# design.net
KiCad netlist of a schematic drawn in EasyEDA Pro
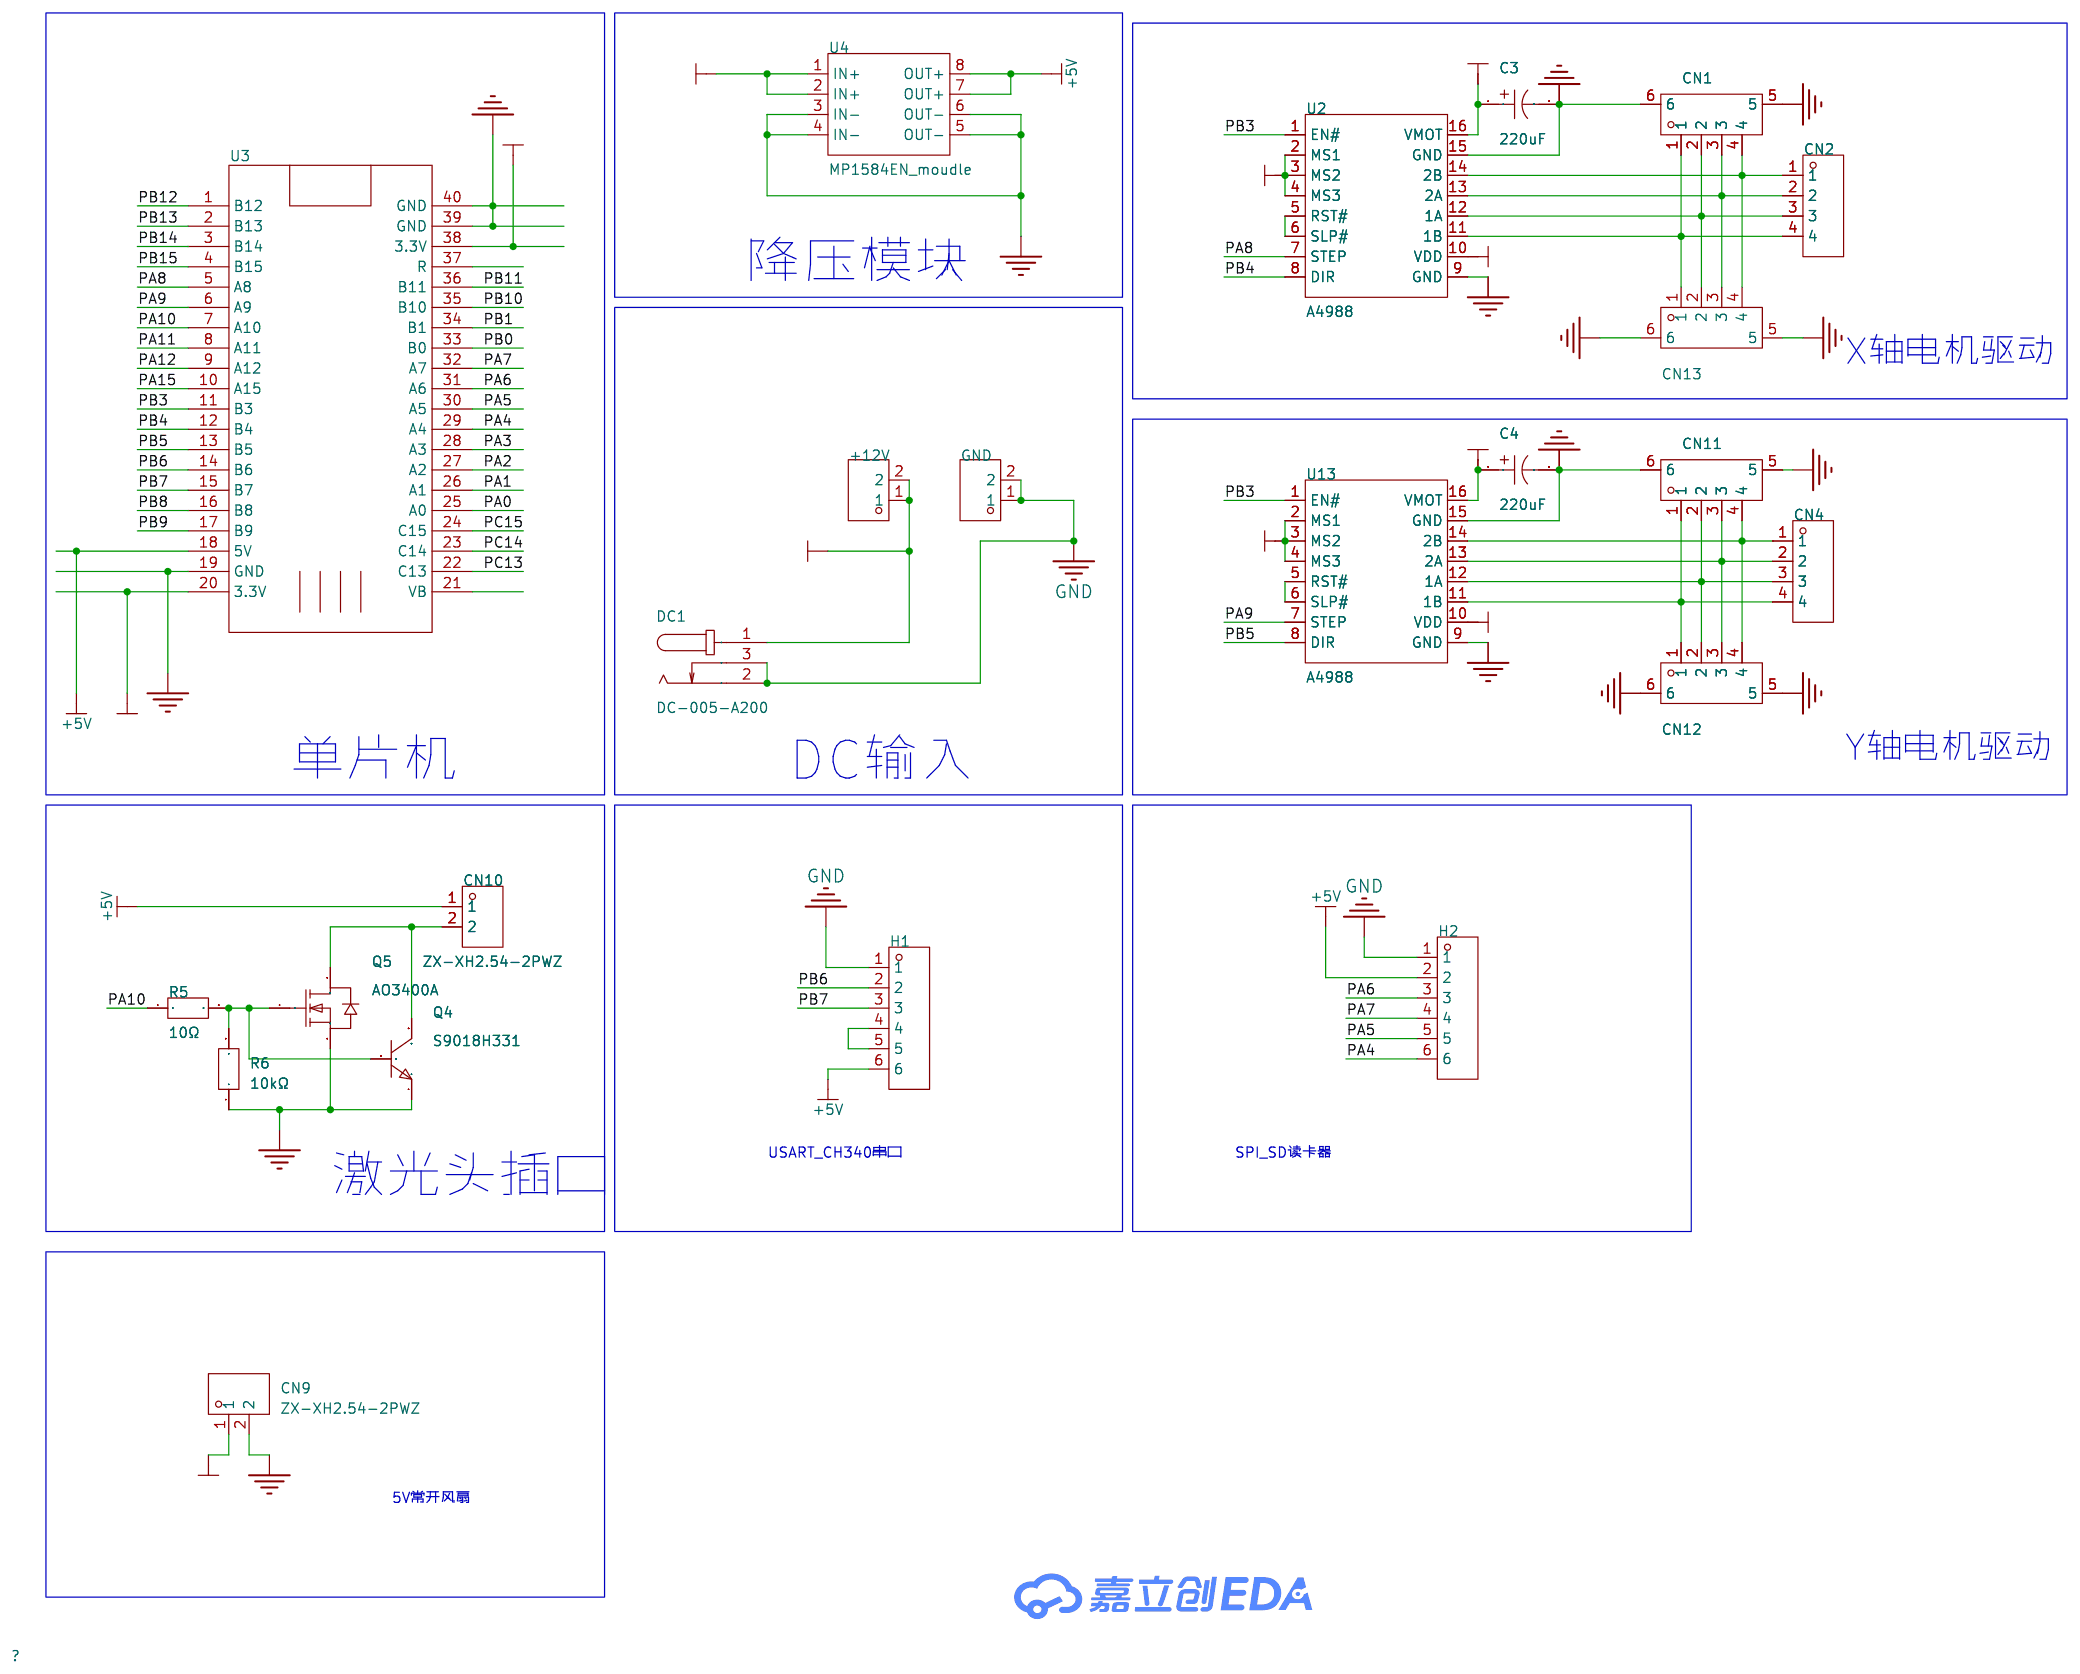
[diagram p0: schematic sheet]

(export (version "E")
  (design (tool "Eeschema 10.0.6"))
  (components
    (comp (ref "+12V")
      (value "~")
      (description "2.54 1*2P 直排针 0.8u镀金 PBT RoHS,针长3*6mm")
      (fields
        (field (name "Manufacturer Part") "Z-211-0211-0021-001")
        (field (name "Manufacturer") "Nextron(台湾正凌)")
      )
      (libsource (lib "easyedapro") (part "Z-211-0211-0021-001"))
    )
    (comp (ref "C3")
      (value "220uF")
      (footprint "easyedapro:CAP-TH_BD8.0-P3.50-D0.6-FD")
      (description "容值:220uF;精度:±20%;额定电压:25V;纹波电流:-;等效串联电阻(ESR):-;")
      (fields
        (field (name "Manufacturer Part") "RA3-25V221MG3#-F1")
        (field (name "Manufacturer") "TAIYO YUDEN(太诱)")
      )
      (libsource (lib "easyedapro") (part "RA3-25V221MG3#-F1"))
    )
    (comp (ref "C4")
      (value "220uF")
      (footprint "easyedapro:CAP-TH_BD8.0-P3.50-D0.6-FD")
      (description "容值:220uF;精度:±20%;额定电压:25V;纹波电流:-;等效串联电阻(ESR):-;")
      (fields
        (field (name "Manufacturer Part") "RA3-25V221MG3#-F1")
        (field (name "Manufacturer") "TAIYO YUDEN(太诱)")
      )
      (libsource (lib "easyedapro") (part "RA3-25V221MG3#-F1"))
    )
    (comp (ref "CN1")
      (value "AFA07-S04ECC-00")
      (footprint "easyedapro:FPC-SMD_4P-P1.00_AFA07-S04ECC-00")
      (description "锁定特性:抽屉式;触点类型:上接;触点数量:4P;间距:1mm;安装类型:卧贴;")
      (fields (field (name "Manufacturer") "JS(钜硕电子)"))
      (libsource (lib "easyedapro") (part "FPCPull type Pick up H3.0mm"))
    )
    (comp (ref "CN2")
      (value "2.54-1*4P母")
      (footprint "easyedapro:HDR-TH_4P-P2.54-V-F")
      (fields (field (name "Manufacturer") "BOOMELE(博穆精密)"))
      (libsource (lib "easyedapro") (part "2.54-1*4P母"))
    )
    (comp (ref "CN4")
      (value "2.54-1*4P母")
      (footprint "easyedapro:HDR-TH_4P-P2.54-V-F")
      (fields (field (name "Manufacturer") "BOOMELE(博穆精密)"))
      (libsource (lib "easyedapro") (part "2.54-1*4P母"))
    )
    (comp (ref "CN9")
      (value "ZX-XH2.54-2PWZ")
      (footprint "easyedapro:CONN-TH_2P-P2.50_ZX-XH2.54-2PWZ")
      (fields (field (name "Manufacturer") "Megastar(兆星)"))
      (libsource (lib "easyedapro") (part "ZX-XH2.54-2PWZ"))
    )
    (comp (ref "CN10")
      (value "ZX-XH2.54-2PWZ")
      (footprint "easyedapro:CONN-TH_2P-P2.50_ZX-XH2.54-2PWZ")
      (fields (field (name "Manufacturer") "Megastar(兆星)"))
      (libsource (lib "easyedapro") (part "ZX-XH2.54-2PWZ"))
    )
    (comp (ref "CN11")
      (value "AFA07-S04ECC-00")
      (footprint "easyedapro:FPC-SMD_4P-P1.00_AFA07-S04ECC-00")
      (description "锁定特性:抽屉式;触点类型:上接;触点数量:4P;间距:1mm;安装类型:卧贴;")
      (fields (field (name "Manufacturer") "JS(钜硕电子)"))
      (libsource (lib "easyedapro") (part "FPCPull type Pick up H3.0mm"))
    )
    (comp (ref "CN12")
      (value "AFA07-S04ECC-00")
      (footprint "easyedapro:FPC-SMD_4P-P1.00_AFA07-S04ECC-00")
      (description "锁定特性:抽屉式;触点类型:上接;触点数量:4P;间距:1mm;安装类型:卧贴;")
      (fields (field (name "Manufacturer") "JS(钜硕电子)"))
      (libsource (lib "easyedapro") (part "FPCPull type Pick up H3.0mm"))
    )
    (comp (ref "CN13")
      (value "AFA07-S04ECC-00")
      (footprint "easyedapro:FPC-SMD_4P-P1.00_AFA07-S04ECC-00")
      (description "锁定特性:抽屉式;触点类型:上接;触点数量:4P;间距:1mm;安装类型:卧贴;")
      (fields (field (name "Manufacturer") "JS(钜硕电子)"))
      (libsource (lib "easyedapro") (part "FPCPull type Pick up H3.0mm"))
    )
    (comp (ref "DC1")
      (value "DC-005-A200")
      (footprint "easyedapro:DC-IN-TH_DC-005-A200")
      (description "连接器类型:DC电源插座;安装方式:弯插;触点内径:2mm;触点外径:6.4mm;额定电流:3A;额定电压:30V;工作温度:-20°C~+70°C;")
      (fields (field (name "Manufacturer") "XUNPU(讯普)"))
      (libsource (lib "easyedapro") (part "DC-005-A200"))
    )
    (comp (ref "GND")
      (value "~")
      (description "2.54 1*2P 直排针 0.8u镀金 PBT RoHS,针长3*6mm")
      (fields
        (field (name "Manufacturer Part") "Z-211-0211-0021-001")
        (field (name "Manufacturer") "Nextron(台湾正凌)")
      )
      (libsource (lib "easyedapro") (part "Z-211-0211-0021-001"))
    )
    (comp (ref "H1")
      (value "~")
      (footprint "easyedapro:HDR-TH_6P-P2.54-V-F")
      (libsource (lib "easyedapro") (part "Header-Female-2.54_1x6"))
    )
    (comp (ref "H2")
      (value "~")
      (footprint "easyedapro:HDR-TH_6P-P2.54-V-F")
      (libsource (lib "easyedapro") (part "Header-Female-2.54_1x6"))
    )
    (comp (ref "Q4")
      (value "S9018H331")
      (footprint "easyedapro:TO-92-3_L4.8-W3.7-P1.27-L-1")
      (fields (field (name "Manufacturer") "ALJ(龙晶微)"))
      (libsource (lib "easyedapro") (part "S9018H331"))
    )
    (comp (ref "Q5")
      (value "AO3400A")
      (footprint "easyedapro:SOT-23-3_L2.9-W1.3-P1.90-LS2.4-BR")
      (description "数量:-;漏源电压(Vdss):30V;连续漏极电流(Id):-;导通电阻(RDS(on)):48mΩ@2.5V;耗散功率(Pd):-;阈值电压(Vgs(th)):1.45V@250uA;")
      (fields (field (name "Manufacturer") "AOS"))
      (libsource (lib "easyedapro") (part "AO3400A"))
    )
    (comp (ref "R5")
      (value "10Ω")
      (footprint "easyedapro:R0603")
      (description "电阻类型:薄膜电阻;阻值:10Ω;精度:±0.1%;功率:100mW;工作电压:75V;温度系数:±25ppm/°C;")
      (fields (field (name "Manufacturer Part") "AT0603BRD0710RL") (field (name "Manufacturer") "YAGEO(国巨)"))
      (libsource (lib "easyedapro") (part "AT0603BRD0710RL"))
    )
    (comp (ref "R6")
      (value "10kΩ")
      (footprint "easyedapro:R0805")
      (description "电阻类型:厚膜电阻;阻值:10kΩ;精度:±1%;功率:500mW;温度系数:±100ppm/°C;")
      (fields (field (name "Manufacturer Part") "SDR10EZPF1002") (field (name "Manufacturer") "ROHM(罗姆)"))
      (libsource (lib "easyedapro") (part "SDR10EZPF1002"))
    )
    (comp (ref "U2")
      (value "A4988")
      (footprint "easyedapro:DIP-16_L20.3-W15.2-P2.54_LS12.7_A4988")
      (libsource (lib "easyedapro") (part "A4988"))
    )
    (comp (ref "U3") (value "~") (libsource (lib "easyedapro") (part "STM32F103C8T6核心板")))
    (comp (ref "U4")
      (value "MP1584EN_moudle")
      (footprint "easyedapro:PWRM-TH_MP1584EN_MOUDLE")
      (libsource (lib "easyedapro") (part "MP1584EN_MOUDLE"))
    )
    (comp (ref "U13")
      (value "A4988")
      (footprint "easyedapro:DIP-16_L20.3-W15.2-P2.54_LS12.7_A4988")
      (libsource (lib "easyedapro") (part "A4988"))
    )
  )
  (nets
    (net (code "1") (name "+3.3V") (class "Default")
      (node (ref "U3") (pin "20") (pinfunction "3.3V_20") (pintype "unspecified"))
      (node (ref "U3") (pin "38") (pinfunction "3.3V_38") (pintype "unspecified"))
    )
    (net (code "2") (name "+5V") (class "Default")
      (node (ref "CN10") (pin "1") (pinfunction "1_1") (pintype "unspecified"))
      (node (ref "CN9") (pin "1") (pinfunction "1_1") (pintype "unspecified"))
      (node (ref "H1") (pin "6") (pinfunction "6_6") (pintype "unspecified"))
      (node (ref "H2") (pin "2") (pinfunction "2_2") (pintype "unspecified"))
      (node (ref "U13") (pin "10") (pinfunction "VDD_10") (pintype "unspecified"))
      (node (ref "U13") (pin "2") (pinfunction "MS1_2") (pintype "unspecified"))
      (node (ref "U13") (pin "3") (pinfunction "MS2_3") (pintype "unspecified"))
      (node (ref "U13") (pin "4") (pinfunction "MS3_4") (pintype "unspecified"))
      (node (ref "U2") (pin "10") (pinfunction "VDD_10") (pintype "unspecified"))
      (node (ref "U2") (pin "2") (pinfunction "MS1_2") (pintype "unspecified"))
      (node (ref "U2") (pin "3") (pinfunction "MS2_3") (pintype "unspecified"))
      (node (ref "U2") (pin "4") (pinfunction "MS3_4") (pintype "unspecified"))
      (node (ref "U3") (pin "18") (pinfunction "5V_18") (pintype "unspecified"))
      (node (ref "U4") (pin "7") (pinfunction "OUT+_7") (pintype "unspecified"))
      (node (ref "U4") (pin "8") (pinfunction "OUT+_8") (pintype "unspecified"))
    )
    (net (code "3") (name "+12V") (class "Default")
      (node (ref "+12V") (pin "1") (pinfunction "1_1") (pintype "input"))
      (node (ref "+12V") (pin "2") (pinfunction "2_2") (pintype "input"))
      (node (ref "C3") (pin "1") (pinfunction "1_1") (pintype "input"))
      (node (ref "C4") (pin "1") (pinfunction "1_1") (pintype "input"))
      (node (ref "DC1") (pin "1") (pinfunction "1_1") (pintype "unspecified"))
      (node (ref "U13") (pin "16") (pinfunction "VMOT_16") (pintype "unspecified"))
      (node (ref "U2") (pin "16") (pinfunction "VMOT_16") (pintype "unspecified"))
      (node (ref "U4") (pin "1") (pinfunction "IN+_1") (pintype "unspecified"))
      (node (ref "U4") (pin "2") (pinfunction "IN+_2") (pintype "unspecified"))
    )
    (net (code "4") (name "/PA0") (class "Default")
      (node (ref "U3") (pin "25") (pinfunction "A0_25") (pintype "unspecified"))
    )
    (net (code "5") (name "/PA1") (class "Default")
      (node (ref "U3") (pin "26") (pinfunction "A1_26") (pintype "unspecified"))
    )
    (net (code "6") (name "/PA2") (class "Default")
      (node (ref "U3") (pin "27") (pinfunction "A2_27") (pintype "unspecified"))
    )
    (net (code "7") (name "/PA3") (class "Default")
      (node (ref "U3") (pin "28") (pinfunction "A3_28") (pintype "unspecified"))
    )
    (net (code "8") (name "/PA4") (class "Default")
      (node (ref "H2") (pin "6") (pinfunction "6_6") (pintype "unspecified"))
      (node (ref "U3") (pin "29") (pinfunction "A4_29") (pintype "unspecified"))
    )
    (net (code "9") (name "/PA5") (class "Default")
      (node (ref "H2") (pin "5") (pinfunction "5_5") (pintype "unspecified"))
      (node (ref "U3") (pin "30") (pinfunction "A5_30") (pintype "unspecified"))
    )
    (net (code "10") (name "/PA6") (class "Default")
      (node (ref "H2") (pin "3") (pinfunction "3_3") (pintype "unspecified"))
      (node (ref "U3") (pin "31") (pinfunction "A6_31") (pintype "unspecified"))
    )
    (net (code "11") (name "/PA7") (class "Default")
      (node (ref "H2") (pin "4") (pinfunction "4_4") (pintype "unspecified"))
      (node (ref "U3") (pin "32") (pinfunction "A7_32") (pintype "unspecified"))
    )
    (net (code "12") (name "/PA8") (class "Default")
      (node (ref "U2") (pin "7") (pinfunction "STEP_7") (pintype "unspecified"))
      (node (ref "U3") (pin "5") (pinfunction "A8_5") (pintype "unspecified"))
    )
    (net (code "13") (name "/PA9") (class "Default")
      (node (ref "U13") (pin "7") (pinfunction "STEP_7") (pintype "unspecified"))
      (node (ref "U3") (pin "6") (pinfunction "A9_6") (pintype "unspecified"))
    )
    (net (code "14") (name "/PA10") (class "Default")
      (node (ref "R5") (pin "1") (pinfunction "1_1") (pintype "unspecified"))
      (node (ref "U3") (pin "7") (pinfunction "A10_7") (pintype "unspecified"))
    )
    (net (code "15") (name "/PA11") (class "Default")
      (node (ref "U3") (pin "8") (pinfunction "A11_8") (pintype "unspecified"))
    )
    (net (code "16") (name "/PA12") (class "Default")
      (node (ref "U3") (pin "9") (pinfunction "A12_9") (pintype "unspecified"))
    )
    (net (code "17") (name "/PA15") (class "Default")
      (node (ref "U3") (pin "10") (pinfunction "A15_10") (pintype "unspecified"))
    )
    (net (code "18") (name "/PB0") (class "Default")
      (node (ref "U3") (pin "33") (pinfunction "B0_33") (pintype "unspecified"))
    )
    (net (code "19") (name "/PB1") (class "Default")
      (node (ref "U3") (pin "34") (pinfunction "B1_34") (pintype "unspecified"))
    )
    (net (code "20") (name "/PB3") (class "Default")
      (node (ref "U13") (pin "1") (pinfunction "EN#_1") (pintype "unspecified"))
      (node (ref "U2") (pin "1") (pinfunction "EN#_1") (pintype "unspecified"))
      (node (ref "U3") (pin "11") (pinfunction "B3_11") (pintype "unspecified"))
    )
    (net (code "21") (name "/PB4") (class "Default")
      (node (ref "U2") (pin "8") (pinfunction "DIR_8") (pintype "unspecified"))
      (node (ref "U3") (pin "12") (pinfunction "B4_12") (pintype "unspecified"))
    )
    (net (code "22") (name "/PB5") (class "Default")
      (node (ref "U13") (pin "8") (pinfunction "DIR_8") (pintype "unspecified"))
      (node (ref "U3") (pin "13") (pinfunction "B5_13") (pintype "unspecified"))
    )
    (net (code "23") (name "/PB6") (class "Default")
      (node (ref "H1") (pin "2") (pinfunction "2_2") (pintype "unspecified"))
      (node (ref "U3") (pin "14") (pinfunction "B6_14") (pintype "unspecified"))
    )
    (net (code "24") (name "/PB7") (class "Default")
      (node (ref "H1") (pin "3") (pinfunction "3_3") (pintype "unspecified"))
      (node (ref "U3") (pin "15") (pinfunction "B7_15") (pintype "unspecified"))
    )
    (net (code "25") (name "/PB8") (class "Default")
      (node (ref "U3") (pin "16") (pinfunction "B8_16") (pintype "unspecified"))
    )
    (net (code "26") (name "/PB9") (class "Default")
      (node (ref "U3") (pin "17") (pinfunction "B9_17") (pintype "unspecified"))
    )
    (net (code "27") (name "/PB10") (class "Default")
      (node (ref "U3") (pin "35") (pinfunction "B10_35") (pintype "unspecified"))
    )
    (net (code "28") (name "/PB11") (class "Default")
      (node (ref "U3") (pin "36") (pinfunction "B11_36") (pintype "unspecified"))
    )
    (net (code "29") (name "/PB12") (class "Default")
      (node (ref "U3") (pin "1") (pinfunction "B12_1") (pintype "unspecified"))
    )
    (net (code "30") (name "/PB13") (class "Default")
      (node (ref "U3") (pin "2") (pinfunction "B13_2") (pintype "unspecified"))
    )
    (net (code "31") (name "/PB14") (class "Default")
      (node (ref "U3") (pin "3") (pinfunction "B14_3") (pintype "unspecified"))
    )
    (net (code "32") (name "/PB15") (class "Default")
      (node (ref "U3") (pin "4") (pinfunction "B15_4") (pintype "unspecified"))
    )
    (net (code "33") (name "/PC13") (class "Default")
      (node (ref "U3") (pin "22") (pinfunction "C13_22") (pintype "unspecified"))
    )
    (net (code "34") (name "/PC14") (class "Default")
      (node (ref "U3") (pin "23") (pinfunction "C14_23") (pintype "unspecified"))
    )
    (net (code "35") (name "/PC15") (class "Default")
      (node (ref "U3") (pin "24") (pinfunction "C15_24") (pintype "unspecified"))
    )
    (net (code "36") (name "GND") (class "Default")
      (node (ref "C3") (pin "2") (pinfunction "2_2") (pintype "input"))
      (node (ref "C4") (pin "2") (pinfunction "2_2") (pintype "input"))
      (node (ref "CN1") (pin "5") (pinfunction "5_5") (pintype "unspecified"))
      (node (ref "CN1") (pin "6") (pinfunction "6_6") (pintype "unspecified"))
      (node (ref "CN11") (pin "5") (pinfunction "5_5") (pintype "unspecified"))
      (node (ref "CN11") (pin "6") (pinfunction "6_6") (pintype "unspecified"))
      (node (ref "CN12") (pin "5") (pinfunction "5_5") (pintype "unspecified"))
      (node (ref "CN12") (pin "6") (pinfunction "6_6") (pintype "unspecified"))
      (node (ref "CN13") (pin "5") (pinfunction "5_5") (pintype "unspecified"))
      (node (ref "CN13") (pin "6") (pinfunction "6_6") (pintype "unspecified"))
      (node (ref "CN9") (pin "2") (pinfunction "2_2") (pintype "unspecified"))
      (node (ref "DC1") (pin "2") (pinfunction "2_2") (pintype "unspecified"))
      (node (ref "DC1") (pin "3") (pinfunction "3_3") (pintype "unspecified"))
      (node (ref "GND") (pin "1") (pinfunction "1_1") (pintype "input"))
      (node (ref "GND") (pin "2") (pinfunction "2_2") (pintype "input"))
      (node (ref "H1") (pin "1") (pinfunction "1_1") (pintype "unspecified"))
      (node (ref "H2") (pin "1") (pinfunction "1_1") (pintype "unspecified"))
      (node (ref "Q4") (pin "1") (pinfunction "E_1") (pintype "input"))
      (node (ref "Q5") (pin "2") (pinfunction "S_2") (pintype "unspecified"))
      (node (ref "R6") (pin "1") (pinfunction "1_1") (pintype "unspecified"))
      (node (ref "U13") (pin "15") (pinfunction "GND_15") (pintype "unspecified"))
      (node (ref "U13") (pin "9") (pinfunction "GND_9") (pintype "unspecified"))
      (node (ref "U2") (pin "15") (pinfunction "GND_15") (pintype "unspecified"))
      (node (ref "U2") (pin "9") (pinfunction "GND_9") (pintype "unspecified"))
      (node (ref "U3") (pin "19") (pinfunction "GND_19") (pintype "unspecified"))
      (node (ref "U3") (pin "39") (pinfunction "GND_39") (pintype "unspecified"))
      (node (ref "U3") (pin "40") (pinfunction "GND_40") (pintype "unspecified"))
      (node (ref "U4") (pin "3") (pinfunction "IN-_3") (pintype "unspecified"))
      (node (ref "U4") (pin "4") (pinfunction "IN-_4") (pintype "unspecified"))
      (node (ref "U4") (pin "5") (pinfunction "OUT-_5") (pintype "unspecified"))
      (node (ref "U4") (pin "6") (pinfunction "OUT-_6") (pintype "unspecified"))
    )
    (net (code "37") (name "Net-(H1-Pad4)") (class "Default")
      (node (ref "H1") (pin "4") (pinfunction "4_4") (pintype "unspecified"))
      (node (ref "H1") (pin "5") (pinfunction "5_5") (pintype "unspecified"))
    )
    (net (code "38") (name "Net-(Q4-B)") (class "Default")
      (node (ref "Q4") (pin "2") (pinfunction "B_2") (pintype "input"))
      (node (ref "Q5") (pin "1") (pinfunction "G_1") (pintype "unspecified"))
      (node (ref "R5") (pin "2") (pinfunction "2_2") (pintype "unspecified"))
      (node (ref "R6") (pin "2") (pinfunction "2_2") (pintype "unspecified"))
    )
    (net (code "39") (name "Net-(Q4-C)") (class "Default")
      (node (ref "CN10") (pin "2") (pinfunction "2_2") (pintype "unspecified"))
      (node (ref "Q4") (pin "3") (pinfunction "C_3") (pintype "input"))
      (node (ref "Q5") (pin "3") (pinfunction "D_3") (pintype "unspecified"))
    )
    (net (code "40") (name "Net-(U2-1A)") (class "Default")
      (node (ref "CN1") (pin "2") (pinfunction "2_2") (pintype "unspecified"))
      (node (ref "CN13") (pin "2") (pinfunction "2_2") (pintype "unspecified"))
      (node (ref "CN2") (pin "3") (pinfunction "3_3") (pintype "unspecified"))
      (node (ref "U2") (pin "12") (pinfunction "1A_12") (pintype "unspecified"))
    )
    (net (code "41") (name "Net-(U2-1B)") (class "Default")
      (node (ref "CN1") (pin "1") (pinfunction "1_1") (pintype "unspecified"))
      (node (ref "CN13") (pin "1") (pinfunction "1_1") (pintype "unspecified"))
      (node (ref "CN2") (pin "4") (pinfunction "4_4") (pintype "unspecified"))
      (node (ref "U2") (pin "11") (pinfunction "1B_11") (pintype "unspecified"))
    )
    (net (code "42") (name "Net-(U2-2A)") (class "Default")
      (node (ref "CN1") (pin "3") (pinfunction "3_3") (pintype "unspecified"))
      (node (ref "CN13") (pin "3") (pinfunction "3_3") (pintype "unspecified"))
      (node (ref "CN2") (pin "2") (pinfunction "2_2") (pintype "unspecified"))
      (node (ref "U2") (pin "13") (pinfunction "2A_13") (pintype "unspecified"))
    )
    (net (code "43") (name "Net-(U2-2B)") (class "Default")
      (node (ref "CN1") (pin "4") (pinfunction "4_4") (pintype "unspecified"))
      (node (ref "CN13") (pin "4") (pinfunction "4_4") (pintype "unspecified"))
      (node (ref "CN2") (pin "1") (pinfunction "1_1") (pintype "unspecified"))
      (node (ref "U2") (pin "14") (pinfunction "2B_14") (pintype "unspecified"))
    )
    (net (code "44") (name "Net-(U2-RST#)") (class "Default")
      (node (ref "U2") (pin "5") (pinfunction "RST#_5") (pintype "unspecified"))
      (node (ref "U2") (pin "6") (pinfunction "SLP#_6") (pintype "unspecified"))
    )
    (net (code "45") (name "Net-(U13-1A)") (class "Default")
      (node (ref "CN11") (pin "2") (pinfunction "2_2") (pintype "unspecified"))
      (node (ref "CN12") (pin "2") (pinfunction "2_2") (pintype "unspecified"))
      (node (ref "CN4") (pin "3") (pinfunction "3_3") (pintype "unspecified"))
      (node (ref "U13") (pin "12") (pinfunction "1A_12") (pintype "unspecified"))
    )
    (net (code "46") (name "Net-(U13-1B)") (class "Default")
      (node (ref "CN11") (pin "1") (pinfunction "1_1") (pintype "unspecified"))
      (node (ref "CN12") (pin "1") (pinfunction "1_1") (pintype "unspecified"))
      (node (ref "CN4") (pin "4") (pinfunction "4_4") (pintype "unspecified"))
      (node (ref "U13") (pin "11") (pinfunction "1B_11") (pintype "unspecified"))
    )
    (net (code "47") (name "Net-(U13-2A)") (class "Default")
      (node (ref "CN11") (pin "3") (pinfunction "3_3") (pintype "unspecified"))
      (node (ref "CN12") (pin "3") (pinfunction "3_3") (pintype "unspecified"))
      (node (ref "CN4") (pin "2") (pinfunction "2_2") (pintype "unspecified"))
      (node (ref "U13") (pin "13") (pinfunction "2A_13") (pintype "unspecified"))
    )
    (net (code "48") (name "Net-(U13-2B)") (class "Default")
      (node (ref "CN11") (pin "4") (pinfunction "4_4") (pintype "unspecified"))
      (node (ref "CN12") (pin "4") (pinfunction "4_4") (pintype "unspecified"))
      (node (ref "CN4") (pin "1") (pinfunction "1_1") (pintype "unspecified"))
      (node (ref "U13") (pin "14") (pinfunction "2B_14") (pintype "unspecified"))
    )
    (net (code "49") (name "Net-(U13-RST#)") (class "Default")
      (node (ref "U13") (pin "5") (pinfunction "RST#_5") (pintype "unspecified"))
      (node (ref "U13") (pin "6") (pinfunction "SLP#_6") (pintype "unspecified"))
    )
    (net (code "50") (name "unconnected-(U3-R-Pad37)") (class "Default")
      (node (ref "U3") (pin "37") (pinfunction "R_37") (pintype "unspecified"))
    )
    (net (code "51") (name "unconnected-(U3-VB-Pad21)") (class "Default")
      (node (ref "U3") (pin "21") (pinfunction "VB_21") (pintype "unspecified"))
    )
  )
)
